# DM3370_Motor.net
KiCad netlist of a schematic drawn in Altium Designer
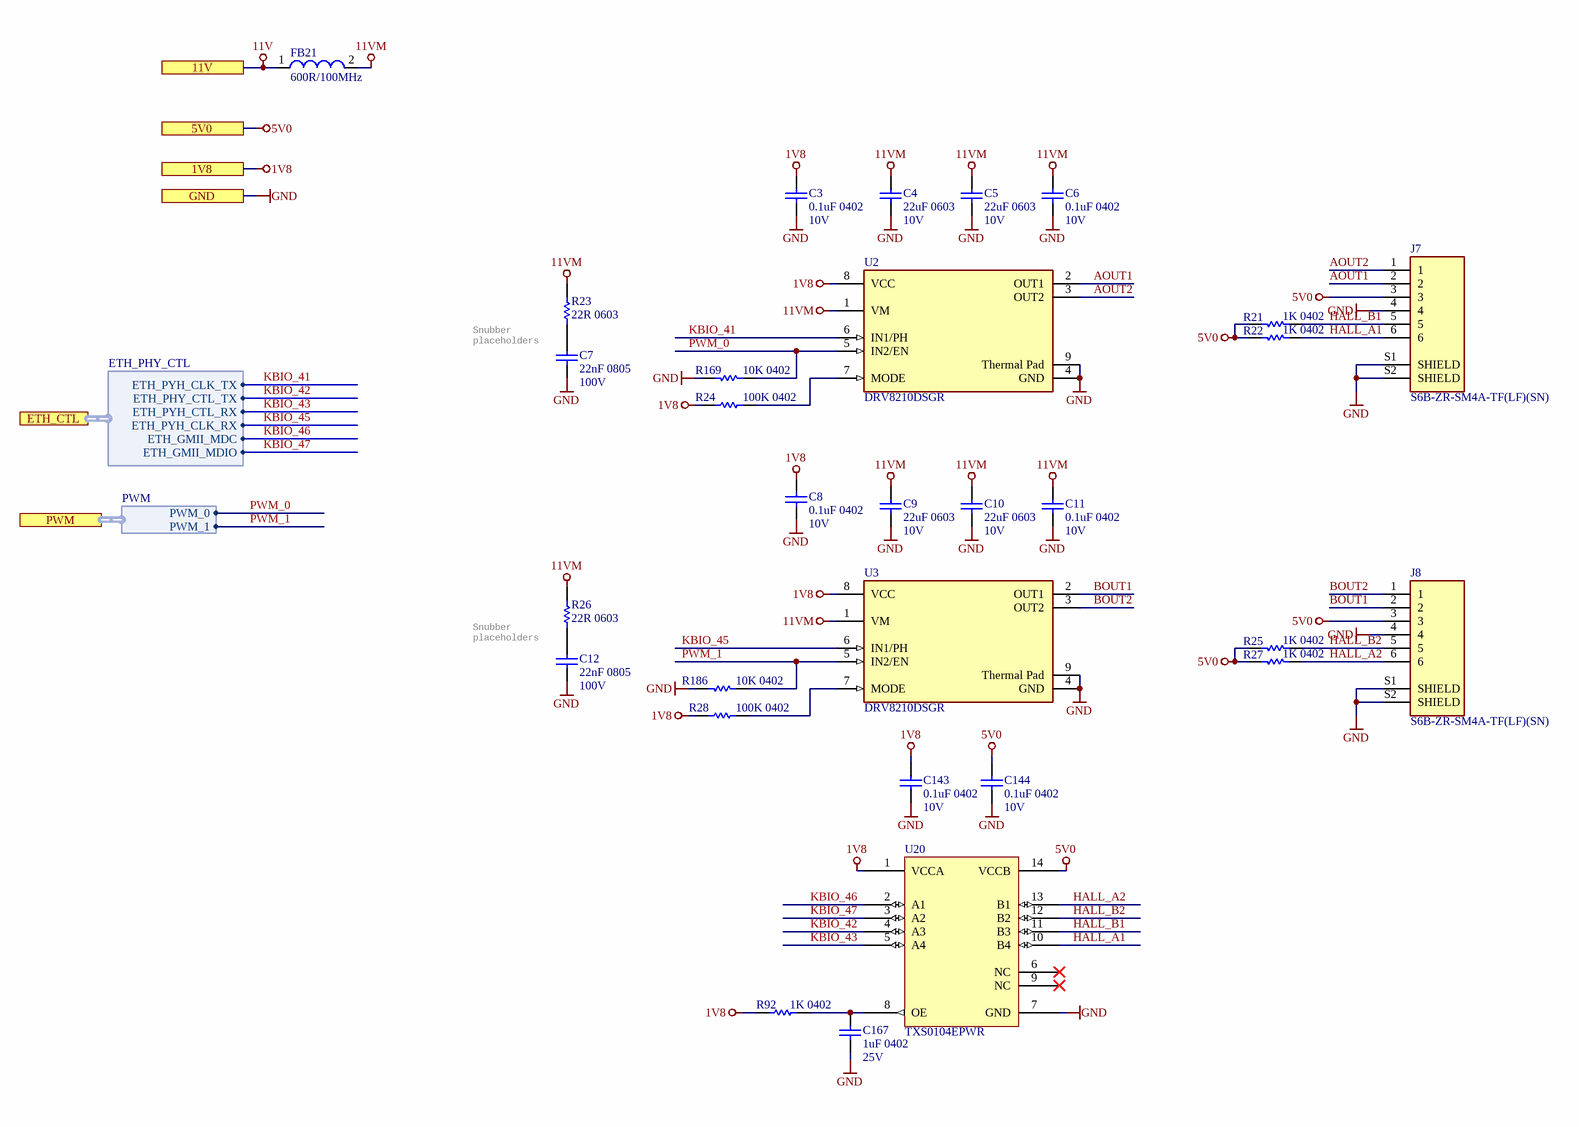
[diagram p0: DM3370_Motor.SchDoc]

(export (version "E")
  (design (tool "Eeschema 10.0.6"))
  (components
    (comp (ref "C3")
      (value "0.1uF 0402")
      (footprint "CAP_Altium_Vault_Generic:CAPC0402(1005)70_L")
      (description "CAP CER 0.1UF 10V X7R 0402 5%")
      (fields (field (name "TOLERANCE") "5%") (field (name "VOLTAGE RATING") "10V"))
      (libsource (lib "LuxonisMaster") (part "GRM155R71A104JA01D"))
    )
    (comp (ref "C4")
      (value "22uF 0603")
      (footprint "CAP_Altium_Vault_Generic:CAPC0603(1608)100_L")
      (description "CAP CER 22UF 10V X5R 0603 20%")
      (fields (field (name "TOLERANCE") "20%") (field (name "VOLTAGE RATING") "10V"))
      (libsource (lib "LuxonisMaster") (part "GRM188R61A226ME15D"))
    )
    (comp (ref "C5")
      (value "22uF 0603")
      (footprint "CAP_Altium_Vault_Generic:CAPC0603(1608)100_L")
      (description "CAP CER 22UF 10V X5R 0603 20%")
      (fields (field (name "TOLERANCE") "20%") (field (name "VOLTAGE RATING") "10V"))
      (libsource (lib "LuxonisMaster") (part "GRM188R61A226ME15D"))
    )
    (comp (ref "C6")
      (value "0.1uF 0402")
      (footprint "CAP_Altium_Vault_Generic:CAPC0402(1005)70_L")
      (description "CAP CER 0.1UF 10V X7R 0402 5%")
      (fields (field (name "TOLERANCE") "5%") (field (name "VOLTAGE RATING") "10V"))
      (libsource (lib "LuxonisMaster") (part "GRM155R71A104JA01D"))
    )
    (comp (ref "C7")
      (value "22nF 0805")
      (footprint "CAP_Altium_Vault_Generic:CAPC0805(2012)145_L")
      (description "CAP CER 22nF 100V X7R 0805")
      (fields (field (name "RATED DC VOLTAGE (URDC)") "100V"))
      (libsource (lib "LuxonisMaster") (part "C0805C223M1RACAUTO"))
    )
    (comp (ref "C8")
      (value "0.1uF 0402")
      (footprint "CAP_Altium_Vault_Generic:CAPC0402(1005)70_L")
      (description "CAP CER 0.1UF 10V X7R 0402 5%")
      (fields (field (name "TOLERANCE") "5%") (field (name "VOLTAGE RATING") "10V"))
      (libsource (lib "LuxonisMaster") (part "GRM155R71A104JA01D"))
    )
    (comp (ref "C9")
      (value "22uF 0603")
      (footprint "CAP_Altium_Vault_Generic:CAPC0603(1608)100_L")
      (description "CAP CER 22UF 10V X5R 0603 20%")
      (fields (field (name "TOLERANCE") "20%") (field (name "VOLTAGE RATING") "10V"))
      (libsource (lib "LuxonisMaster") (part "GRM188R61A226ME15D"))
    )
    (comp (ref "C10")
      (value "22uF 0603")
      (footprint "CAP_Altium_Vault_Generic:CAPC0603(1608)100_L")
      (description "CAP CER 22UF 10V X5R 0603 20%")
      (fields (field (name "TOLERANCE") "20%") (field (name "VOLTAGE RATING") "10V"))
      (libsource (lib "LuxonisMaster") (part "GRM188R61A226ME15D"))
    )
    (comp (ref "C11")
      (value "0.1uF 0402")
      (footprint "CAP_Altium_Vault_Generic:CAPC0402(1005)70_L")
      (description "CAP CER 0.1UF 10V X7R 0402 5%")
      (fields (field (name "TOLERANCE") "5%") (field (name "VOLTAGE RATING") "10V"))
      (libsource (lib "LuxonisMaster") (part "GRM155R71A104JA01D"))
    )
    (comp (ref "C12")
      (value "22nF 0805")
      (footprint "CAP_Altium_Vault_Generic:CAPC0805(2012)145_L")
      (description "CAP CER 22nF 100V X7R 0805")
      (fields (field (name "RATED DC VOLTAGE (URDC)") "100V"))
      (libsource (lib "LuxonisMaster") (part "C0805C223M1RACAUTO"))
    )
    (comp (ref "C143")
      (value "0.1uF 0402")
      (footprint "CAP_Altium_Vault_Generic:CAPC0402(1005)70_L")
      (description "CAP CER 0.1UF 10V X7R 0402 5%")
      (fields (field (name "TOLERANCE") "5%") (field (name "VOLTAGE RATING") "10V"))
      (libsource (lib "LuxonisMaster") (part "GRM155R71A104JA01D"))
    )
    (comp (ref "C144")
      (value "0.1uF 0402")
      (footprint "CAP_Altium_Vault_Generic:CAPC0402(1005)70_L")
      (description "CAP CER 0.1UF 10V X7R 0402 5%")
      (fields (field (name "TOLERANCE") "5%") (field (name "VOLTAGE RATING") "10V"))
      (libsource (lib "LuxonisMaster") (part "GRM155R71A104JA01D"))
    )
    (comp (ref "C167")
      (value "1uF 0402")
      (footprint "CAP_Altium_Vault_Generic:CAPC0402(1005)70_L")
      (description "CAP CER 1UF 25V X5R 0402 10%")
      (fields
        (field (name "TOLERANCE") "10%")
        (field (name "VOLTAGE") "25V")
        (field (name "VOLTAGE RATING") "25V")
      )
      (libsource (lib "LuxonisMaster") (part "GRM155R61E105KA12D"))
    )
    (comp (ref "FB21")
      (value "600R/100MHz")
      (footprint "LuxonisMaster:2508056017Y2")
      (description "FERRITE BEAD, 0.1OHM, 2A, 0805, 600R/100MHz")
      (fields (field (name "TOLERANCE") "25%"))
      (libsource (lib "LuxonisMaster") (part "2508056017Y2"))
    )
    (comp (ref "J7")
      (value "S6B-ZR-SM4A-TF(LF)(SN)")
      (footprint "FP-S6B-ZR-SM4A-TF_LF_SN-MFG")
      (description "Connector Header, ZH Series, 6 Position, 1.5mm, Surface Mount Right Angle, Detent Lock, Natural")
      (libsource (lib "Luxonis LLC") (part "S6B-ZR"))
    )
    (comp (ref "J8")
      (value "S6B-ZR-SM4A-TF(LF)(SN)")
      (footprint "FP-S6B-ZR-SM4A-TF_LF_SN-MFG")
      (description "Connector Header, ZH Series, 6 Position, 1.5mm, Surface Mount Right Angle, Detent Lock, Natural")
      (libsource (lib "Luxonis LLC") (part "S6B-ZR"))
    )
    (comp (ref "R21")
      (value "1K 0402")
      (footprint "RES_Altium_Vault_Generic:RESC0402(1005)_L")
      (fields (field (name "TOLERANCE") "1%"))
      (libsource (lib "LuxonisMaster") (part "RC0402FR-071KL"))
    )
    (comp (ref "R22")
      (value "1K 0402")
      (footprint "RES_Altium_Vault_Generic:RESC0402(1005)_L")
      (fields (field (name "TOLERANCE") "1%"))
      (libsource (lib "LuxonisMaster") (part "RC0402FR-071KL"))
    )
    (comp (ref "R23")
      (value "22R 0603")
      (footprint "RES_Altium_Vault_Generic:RESC0603(1608)_L")
      (description "RES SMD 22 OHM 1% 1/10W 0603")
      (fields (field (name "TOLERANCE") "1%"))
      (libsource (lib "LuxonisMaster") (part "RC0603FR-0722RL"))
    )
    (comp (ref "R24")
      (value "100K 0402")
      (footprint "RES_Altium_Vault_Generic:RESC0402(1005)_L")
      (description "RES SMD 100K OHM 1% 1/16W 0402")
      (fields (field (name "TOLERANCE") "1%"))
      (libsource (lib "LuxonisMaster") (part "RC0402FR-07100KL"))
    )
    (comp (ref "R25")
      (value "1K 0402")
      (footprint "RES_Altium_Vault_Generic:RESC0402(1005)_L")
      (fields (field (name "TOLERANCE") "1%"))
      (libsource (lib "LuxonisMaster") (part "RC0402FR-071KL"))
    )
    (comp (ref "R26")
      (value "22R 0603")
      (footprint "RES_Altium_Vault_Generic:RESC0603(1608)_L")
      (description "RES SMD 22 OHM 1% 1/10W 0603")
      (fields (field (name "TOLERANCE") "1%"))
      (libsource (lib "LuxonisMaster") (part "RC0603FR-0722RL"))
    )
    (comp (ref "R27")
      (value "1K 0402")
      (footprint "RES_Altium_Vault_Generic:RESC0402(1005)_L")
      (fields (field (name "TOLERANCE") "1%"))
      (libsource (lib "LuxonisMaster") (part "RC0402FR-071KL"))
    )
    (comp (ref "R28")
      (value "100K 0402")
      (footprint "RES_Altium_Vault_Generic:RESC0402(1005)_L")
      (description "RES SMD 100K OHM 1% 1/16W 0402")
      (fields (field (name "TOLERANCE") "1%"))
      (libsource (lib "LuxonisMaster") (part "RC0402FR-07100KL"))
    )
    (comp (ref "R92")
      (value "1K 0402")
      (footprint "RES_Altium_Vault_Generic:RESC0402(1005)_L")
      (fields (field (name "TOLERANCE") "1%"))
      (libsource (lib "LuxonisMaster") (part "RC0402FR-071KL"))
    )
    (comp (ref "R169")
      (value "10K 0402")
      (footprint "RES_Altium_Vault_Generic:RESC0402(1005)_L")
      (fields (field (name "TOLERANCE") "1%"))
      (libsource (lib "LuxonisMaster") (part "RC0402FR-1310KL"))
    )
    (comp (ref "R186")
      (value "10K 0402")
      (footprint "RES_Altium_Vault_Generic:RESC0402(1005)_L")
      (fields (field (name "TOLERANCE") "1%"))
      (libsource (lib "LuxonisMaster") (part "RC0402FR-1310KL"))
    )
    (comp (ref "U2")
      (value "DRV8210DSGR")
      (footprint "FP-DSG0008A-MFG")
      (description "11V, 1A BRUSHED DC MOTOR DRIVER")
      (libsource (lib "Luxonis LLC") (part "DRV8210DSGR"))
    )
    (comp (ref "U3")
      (value "DRV8210DSGR")
      (footprint "FP-DSG0008A-MFG")
      (description "11V, 1A BRUSHED DC MOTOR DRIVER")
      (libsource (lib "Luxonis LLC") (part "DRV8210DSGR"))
    )
    (comp (ref "U20")
      (value "TXS0104EPWR")
      (footprint "TXS0104EPWR")
      (description "Interface Circuit, PDSO14")
      (libsource (lib "Luxonis LLC") (part "TXS0104EPWR"))
    )
  )
  (nets
    (net (code "3") (name "/AOUT1") (class "Default")
      (node (ref "J7") (pin "2") (pinfunction "2_2") (pintype "passive"))
      (node (ref "U2") (pin "2") (pinfunction "OUT1_2") (pintype "passive"))
    )
    (net (code "4") (name "/AOUT2") (class "Default")
      (node (ref "J7") (pin "1") (pinfunction "1_1") (pintype "passive"))
      (node (ref "U2") (pin "3") (pinfunction "OUT2_3") (pintype "passive"))
    )
    (net (code "5") (name "/BOUT1") (class "Default")
      (node (ref "J8") (pin "2") (pinfunction "2_2") (pintype "passive"))
      (node (ref "U3") (pin "2") (pinfunction "OUT1_2") (pintype "passive"))
    )
    (net (code "6") (name "/BOUT2") (class "Default")
      (node (ref "J8") (pin "1") (pinfunction "1_1") (pintype "passive"))
      (node (ref "U3") (pin "3") (pinfunction "OUT2_3") (pintype "passive"))
    )
    (net (code "7") (name "/HALL_A1") (class "Default")
      (node (ref "J7") (pin "6") (pinfunction "6_6") (pintype "passive"))
      (node (ref "R22") (pin "1") (pinfunction "1_1") (pintype "passive"))
      (node (ref "U20") (pin "10") (pinfunction "B4_10") (pintype "bidirectional"))
    )
    (net (code "8") (name "/HALL_A2") (class "Default")
      (node (ref "J8") (pin "6") (pinfunction "6_6") (pintype "passive"))
      (node (ref "R27") (pin "1") (pinfunction "1_1") (pintype "passive"))
      (node (ref "U20") (pin "13") (pinfunction "B1_13") (pintype "bidirectional"))
    )
    (net (code "9") (name "/HALL_B1") (class "Default")
      (node (ref "J7") (pin "5") (pinfunction "5_5") (pintype "passive"))
      (node (ref "R21") (pin "1") (pinfunction "1_1") (pintype "passive"))
      (node (ref "U20") (pin "11") (pinfunction "B3_11") (pintype "bidirectional"))
    )
    (net (code "10") (name "/HALL_B2") (class "Default")
      (node (ref "J8") (pin "5") (pinfunction "5_5") (pintype "passive"))
      (node (ref "R25") (pin "1") (pinfunction "1_1") (pintype "passive"))
      (node (ref "U20") (pin "12") (pinfunction "B2_12") (pintype "bidirectional"))
    )
    (net (code "11") (name "/KBIO_41") (class "Default")
      (node (ref "U2") (pin "6") (pinfunction "IN1/PH_6") (pintype "input"))
    )
    (net (code "12") (name "/KBIO_42") (class "Default")
      (node (ref "U20") (pin "4") (pinfunction "A3_4") (pintype "bidirectional"))
    )
    (net (code "13") (name "/KBIO_43") (class "Default")
      (node (ref "U20") (pin "5") (pinfunction "A4_5") (pintype "bidirectional"))
    )
    (net (code "14") (name "/KBIO_45") (class "Default")
      (node (ref "U3") (pin "6") (pinfunction "IN1/PH_6") (pintype "input"))
    )
    (net (code "15") (name "/KBIO_46") (class "Default")
      (node (ref "U20") (pin "2") (pinfunction "A1_2") (pintype "bidirectional"))
    )
    (net (code "16") (name "/KBIO_47") (class "Default")
      (node (ref "U20") (pin "3") (pinfunction "A2_3") (pintype "bidirectional"))
    )
    (net (code "17") (name "/PWM_0") (class "Default")
      (node (ref "R169") (pin "1") (pinfunction "1_1") (pintype "passive"))
      (node (ref "U2") (pin "5") (pinfunction "IN2/EN_5") (pintype "input"))
    )
    (net (code "18") (name "/PWM_1") (class "Default")
      (node (ref "R186") (pin "1") (pinfunction "1_1") (pintype "passive"))
      (node (ref "U3") (pin "5") (pinfunction "IN2/EN_5") (pintype "input"))
    )
    (net (code "21") (name "1V8") (class "Default")
      (node (ref "C143") (pin "2") (pinfunction "2_2") (pintype "passive"))
      (node (ref "C3") (pin "2") (pinfunction "2_2") (pintype "passive"))
      (node (ref "C8") (pin "2") (pinfunction "2_2") (pintype "passive"))
      (node (ref "R24") (pin "1") (pinfunction "1_1") (pintype "passive"))
      (node (ref "R28") (pin "1") (pinfunction "1_1") (pintype "passive"))
      (node (ref "R92") (pin "2") (pinfunction "2_2") (pintype "passive"))
      (node (ref "U2") (pin "8") (pinfunction "VCC_8") (pintype "power_in"))
      (node (ref "U20") (pin "1") (pinfunction "VCCA_1") (pintype "power_in"))
      (node (ref "U3") (pin "8") (pinfunction "VCC_8") (pintype "power_in"))
    )
    (net (code "22") (name "5V0") (class "Default")
      (node (ref "C144") (pin "2") (pinfunction "2_2") (pintype "passive"))
      (node (ref "J7") (pin "3") (pinfunction "3_3") (pintype "passive"))
      (node (ref "J8") (pin "3") (pinfunction "3_3") (pintype "passive"))
      (node (ref "R21") (pin "2") (pinfunction "2_2") (pintype "passive"))
      (node (ref "R22") (pin "2") (pinfunction "2_2") (pintype "passive"))
      (node (ref "R25") (pin "2") (pinfunction "2_2") (pintype "passive"))
      (node (ref "R27") (pin "2") (pinfunction "2_2") (pintype "passive"))
      (node (ref "U20") (pin "14") (pinfunction "VCCB_14") (pintype "power_in"))
    )
    (net (code "23") (name "11V") (class "Default")
      (node (ref "FB21") (pin "1") (pinfunction "1_1") (pintype "passive"))
    )
    (net (code "24") (name "11VM") (class "Default")
      (node (ref "C10") (pin "2") (pinfunction "2_2") (pintype "passive"))
      (node (ref "C11") (pin "2") (pinfunction "2_2") (pintype "passive"))
      (node (ref "C4") (pin "2") (pinfunction "2_2") (pintype "passive"))
      (node (ref "C5") (pin "2") (pinfunction "2_2") (pintype "passive"))
      (node (ref "C6") (pin "2") (pinfunction "2_2") (pintype "passive"))
      (node (ref "C9") (pin "2") (pinfunction "2_2") (pintype "passive"))
      (node (ref "FB21") (pin "2") (pinfunction "2_2") (pintype "passive"))
      (node (ref "R23") (pin "2") (pinfunction "2_2") (pintype "passive"))
      (node (ref "R26") (pin "2") (pinfunction "2_2") (pintype "passive"))
      (node (ref "U2") (pin "1") (pinfunction "VM_1") (pintype "power_in"))
      (node (ref "U3") (pin "1") (pinfunction "VM_1") (pintype "power_in"))
    )
    (net (code "25") (name "GND") (class "Default")
      (node (ref "C10") (pin "1") (pinfunction "1_1") (pintype "passive"))
      (node (ref "C11") (pin "1") (pinfunction "1_1") (pintype "passive"))
      (node (ref "C12") (pin "1") (pinfunction "1_1") (pintype "passive"))
      (node (ref "C143") (pin "1") (pinfunction "1_1") (pintype "passive"))
      (node (ref "C144") (pin "1") (pinfunction "1_1") (pintype "passive"))
      (node (ref "C167") (pin "1") (pinfunction "1_1") (pintype "passive"))
      (node (ref "C3") (pin "1") (pinfunction "1_1") (pintype "passive"))
      (node (ref "C4") (pin "1") (pinfunction "1_1") (pintype "passive"))
      (node (ref "C5") (pin "1") (pinfunction "1_1") (pintype "passive"))
      (node (ref "C6") (pin "1") (pinfunction "1_1") (pintype "passive"))
      (node (ref "C7") (pin "1") (pinfunction "1_1") (pintype "passive"))
      (node (ref "C8") (pin "1") (pinfunction "1_1") (pintype "passive"))
      (node (ref "C9") (pin "1") (pinfunction "1_1") (pintype "passive"))
      (node (ref "J7") (pin "4") (pinfunction "4_4") (pintype "passive"))
      (node (ref "J7") (pin "S1") (pinfunction "SHIELD_S1") (pintype "passive"))
      (node (ref "J7") (pin "S2") (pinfunction "SHIELD_S2") (pintype "passive"))
      (node (ref "J8") (pin "4") (pinfunction "4_4") (pintype "passive"))
      (node (ref "J8") (pin "S1") (pinfunction "SHIELD_S1") (pintype "passive"))
      (node (ref "J8") (pin "S2") (pinfunction "SHIELD_S2") (pintype "passive"))
      (node (ref "R169") (pin "2") (pinfunction "2_2") (pintype "passive"))
      (node (ref "R186") (pin "2") (pinfunction "2_2") (pintype "passive"))
      (node (ref "U2") (pin "4") (pinfunction "GND_4") (pintype "power_in"))
      (node (ref "U2") (pin "9") (pinfunction "Thermal_Pad_9") (pintype "power_in"))
      (node (ref "U20") (pin "7") (pinfunction "GND_7") (pintype "power_in"))
      (node (ref "U3") (pin "4") (pinfunction "GND_4") (pintype "power_in"))
      (node (ref "U3") (pin "9") (pinfunction "Thermal_Pad_9") (pintype "power_in"))
    )
    (net (code "26") (name "Net-(C7-Pad2)") (class "Default")
      (node (ref "C7") (pin "2") (pinfunction "2_2") (pintype "passive"))
      (node (ref "R23") (pin "1") (pinfunction "1_1") (pintype "passive"))
    )
    (net (code "27") (name "Net-(C12-Pad2)") (class "Default")
      (node (ref "C12") (pin "2") (pinfunction "2_2") (pintype "passive"))
      (node (ref "R26") (pin "1") (pinfunction "1_1") (pintype "passive"))
    )
    (net (code "28") (name "Net-(U2-MODE)") (class "Default")
      (node (ref "R24") (pin "2") (pinfunction "2_2") (pintype "passive"))
      (node (ref "U2") (pin "7") (pinfunction "MODE_7") (pintype "input"))
    )
    (net (code "29") (name "Net-(U3-MODE)") (class "Default")
      (node (ref "R28") (pin "2") (pinfunction "2_2") (pintype "passive"))
      (node (ref "U3") (pin "7") (pinfunction "MODE_7") (pintype "input"))
    )
    (net (code "30") (name "Net-(U20-OE)") (class "Default")
      (node (ref "C167") (pin "2") (pinfunction "2_2") (pintype "passive"))
      (node (ref "R92") (pin "1") (pinfunction "1_1") (pintype "passive"))
      (node (ref "U20") (pin "8") (pinfunction "OE_8") (pintype "output"))
    )
    (net (code "31") (name "unconnected-(U20-NC-Pad6)") (class "Default")
      (node (ref "U20") (pin "6") (pinfunction "NC_6") (pintype "passive+no_connect"))
    )
    (net (code "32") (name "unconnected-(U20-NC-Pad9)") (class "Default")
      (node (ref "U20") (pin "9") (pinfunction "NC_9") (pintype "passive+no_connect"))
    )
  )
)
